# solenoid_drv.net
KiCad netlist of a schematic drawn in Altium Designer
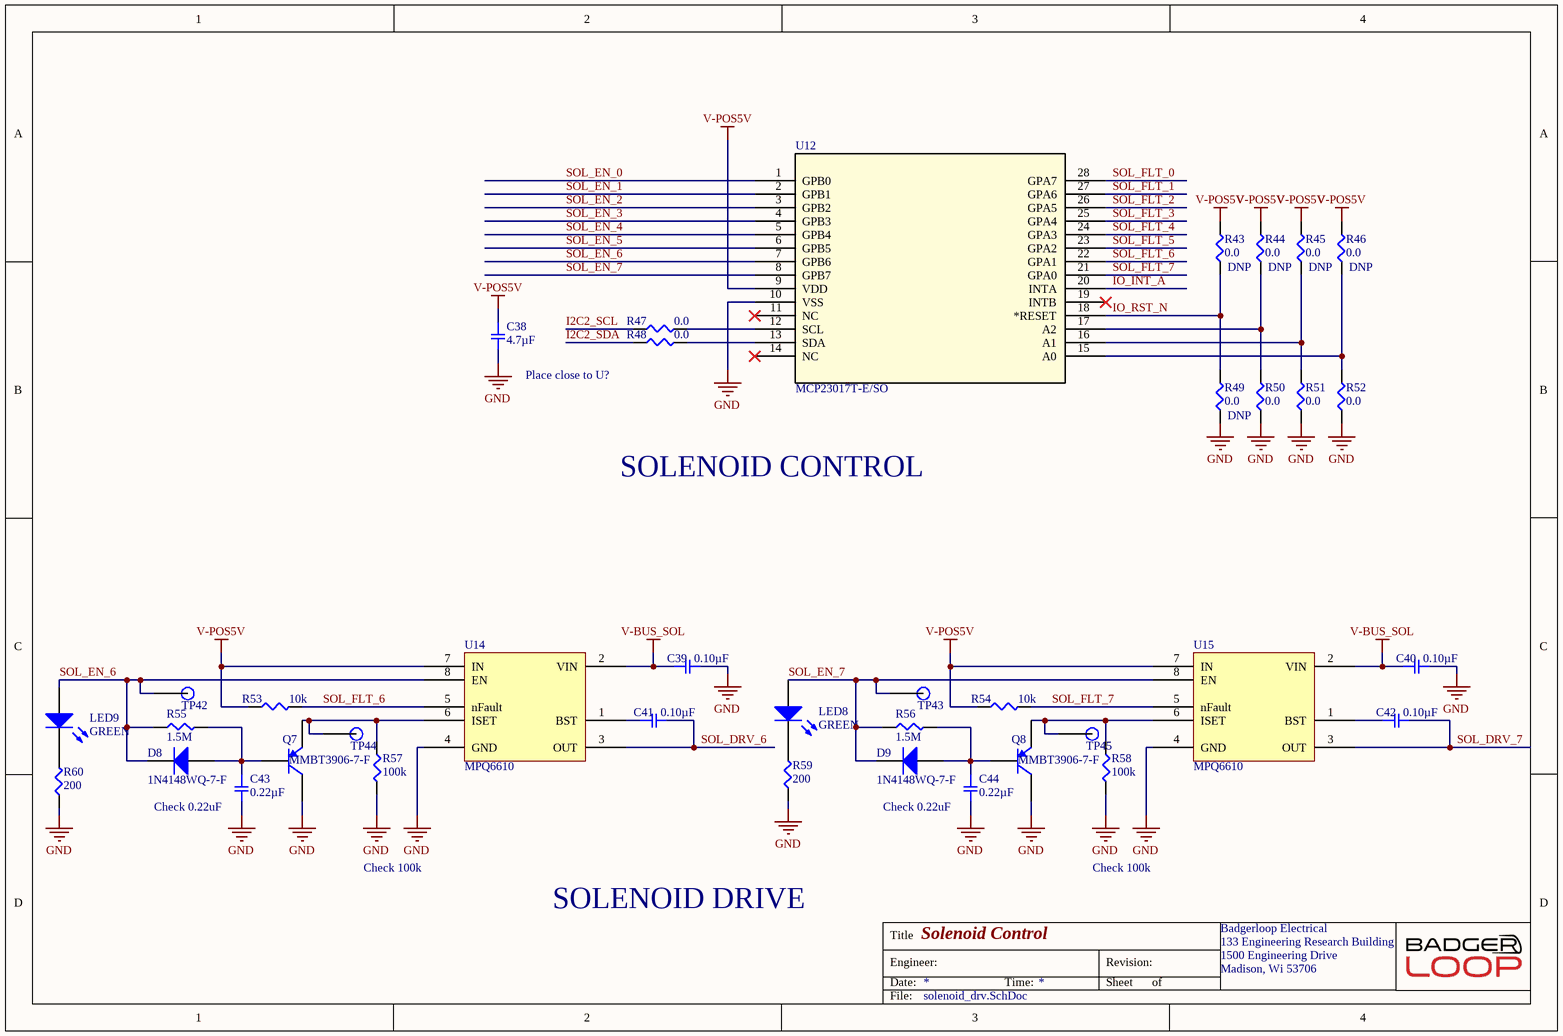
[diagram p0: solenoid_drv.SchDoc]

(export (version "E")
  (design (tool "Eeschema 10.0.6"))
  (components
    (comp (ref "C38")
      (value "4.7µF")
      (footprint "SMD-0805C")
      (description "CAP CER 4.7UF 6.3V X5R 0805")
      (fields
        (field (name "DIGI-KEY PART NUMBER") "490-9749-1-ND")
        (field (name "PART NUMBER") "GRM21BR60J475KA11L")
      )
      (libsource (lib "capacitor") (part "GRM21BR60J475KA11L"))
    )
    (comp (ref "C39")
      (value "0.10µF")
      (footprint "SMD-0805C")
      (description "CAP CER 0.1UF 10V U2J 0805")
      (fields
        (field (name "DIGI-KEY PART NUMBER") "490-11592-1-ND")
        (field (name "PART NUMBER") "GRM21B7U1A104JA01L")
      )
      (libsource (lib "capacitors") (part "GRM21B7U1A104JA01L"))
    )
    (comp (ref "C40")
      (value "0.10µF")
      (footprint "SMD-0805C")
      (description "CAP CER 0.1UF 10V U2J 0805")
      (fields
        (field (name "DIGI-KEY PART NUMBER") "490-11592-1-ND")
        (field (name "PART NUMBER") "GRM21B7U1A104JA01L")
      )
      (libsource (lib "capacitors") (part "GRM21B7U1A104JA01L"))
    )
    (comp (ref "C41")
      (value "0.10µF")
      (footprint "SMD-0805C")
      (description "CAP CER 0.1UF 10V U2J 0805")
      (fields
        (field (name "DIGI-KEY PART NUMBER") "490-11592-1-ND")
        (field (name "PART NUMBER") "GRM21B7U1A104JA01L")
      )
      (libsource (lib "capacitors") (part "GRM21B7U1A104JA01L"))
    )
    (comp (ref "C42")
      (value "0.10µF")
      (footprint "SMD-0805C")
      (description "CAP CER 0.1UF 10V U2J 0805")
      (fields
        (field (name "DIGI-KEY PART NUMBER") "490-11592-1-ND")
        (field (name "PART NUMBER") "GRM21B7U1A104JA01L")
      )
      (libsource (lib "capacitors") (part "GRM21B7U1A104JA01L"))
    )
    (comp (ref "C43")
      (value "0.22µF")
      (footprint "SMD-0805C")
      (description "CAP CER 0.22UF 10V X7R 0805")
      (fields
        (field (name "DIGI-KEY PART NUMBER") "490-4432-1-ND")
        (field (name "PART NUMBER") "LLA215R71A224MA14L")
      )
      (libsource (lib "capacitors") (part "LLA215R71A224MA14L"))
    )
    (comp (ref "C44")
      (value "0.22µF")
      (footprint "SMD-0805C")
      (description "CAP CER 0.22UF 10V X7R 0805")
      (fields
        (field (name "DIGI-KEY PART NUMBER") "490-4432-1-ND")
        (field (name "PART NUMBER") "LLA215R71A224MA14L")
      )
      (libsource (lib "capacitors") (part "LLA215R71A224MA14L"))
    )
    (comp (ref "D8")
      (value "1N4148WQ-7-F")
      (footprint "INDM3838X18N")
      (description "Diodes - General Purpose, Power, Switching SMT Fast Switching Diode")
      (fields (field (name "MANUFACTURER") "Diodes Inc."))
      (libsource (lib "misc") (part "1N4148WQ-7-F"))
    )
    (comp (ref "D9")
      (value "1N4148WQ-7-F")
      (footprint "INDM3838X18N")
      (description "Diodes - General Purpose, Power, Switching SMT Fast Switching Diode")
      (fields (field (name "MANUFACTURER") "Diodes Inc."))
      (libsource (lib "misc") (part "1N4148WQ-7-F"))
    )
    (comp (ref "LED8")
      (value "GREEN")
      (footprint "LED 0603 GREEN")
      (fields (field (name "MANUFACTURER") "Lite-On Inc."))
      (libsource (lib "misc") (part "LED GREEN 0603"))
    )
    (comp (ref "LED9")
      (value "GREEN")
      (footprint "LED 0603 GREEN")
      (fields (field (name "MANUFACTURER") "Lite-On Inc."))
      (libsource (lib "misc") (part "LED GREEN 0603"))
    )
    (comp (ref "Q7")
      (value "MMBT3906-7-F")
      (footprint "SOTFL103P240X110-3N")
      (fields (field (name "MANUFACTURER") "Diodes Zetex"))
      (libsource (lib "misc") (part "MMBT3906-7-F"))
    )
    (comp (ref "Q8")
      (value "MMBT3906-7-F")
      (footprint "SOTFL103P240X110-3N")
      (fields (field (name "MANUFACTURER") "Diodes Zetex"))
      (libsource (lib "misc") (part "MMBT3906-7-F"))
    )
    (comp (ref "R43")
      (value "0.0")
      (footprint "SMD-0805-RES")
      (description "RES SMD 0.0 OHM JUMPER 1/8W 0805")
      (fields
        (field (name "PART NUMBER") "ERJ-6GEY0R00V")
        (field (name "DIGI-KEY PART NUMBER") "P0.0ACT-ND")
        (field (name "DNP") "DNP")
      )
      (libsource (lib "resistors") (part "ERJ-6GEY0R00V"))
    )
    (comp (ref "R44")
      (value "0.0")
      (footprint "SMD-0805-RES")
      (description "RES SMD 0.0 OHM JUMPER 1/8W 0805")
      (fields
        (field (name "PART NUMBER") "ERJ-6GEY0R00V")
        (field (name "DIGI-KEY PART NUMBER") "P0.0ACT-ND")
        (field (name "DNP") "DNP")
      )
      (libsource (lib "resistors") (part "ERJ-6GEY0R00V"))
    )
    (comp (ref "R45")
      (value "0.0")
      (footprint "SMD-0805-RES")
      (description "RES SMD 0.0 OHM JUMPER 1/8W 0805")
      (fields
        (field (name "PART NUMBER") "ERJ-6GEY0R00V")
        (field (name "DIGI-KEY PART NUMBER") "P0.0ACT-ND")
        (field (name "DNP") "DNP")
      )
      (libsource (lib "resistors") (part "ERJ-6GEY0R00V"))
    )
    (comp (ref "R46")
      (value "0.0")
      (footprint "SMD-0805-RES")
      (description "RES SMD 0.0 OHM JUMPER 1/8W 0805")
      (fields
        (field (name "PART NUMBER") "ERJ-6GEY0R00V")
        (field (name "DIGI-KEY PART NUMBER") "P0.0ACT-ND")
        (field (name "DNP") "DNP")
      )
      (libsource (lib "resistors") (part "ERJ-6GEY0R00V"))
    )
    (comp (ref "R47")
      (value "0.0")
      (footprint "SMD-0805-RES")
      (description "RES SMD 0.0 OHM JUMPER 1/8W 0805")
      (fields (field (name "PART NUMBER") "ERJ-6GEY0R00V") (field (name "DIGI-KEY PART NUMBER") "P0.0ACT-ND"))
      (libsource (lib "resistors") (part "ERJ-6GEY0R00V"))
    )
    (comp (ref "R48")
      (value "0.0")
      (footprint "SMD-0805-RES")
      (description "RES SMD 0.0 OHM JUMPER 1/8W 0805")
      (fields (field (name "PART NUMBER") "ERJ-6GEY0R00V") (field (name "DIGI-KEY PART NUMBER") "P0.0ACT-ND"))
      (libsource (lib "resistors") (part "ERJ-6GEY0R00V"))
    )
    (comp (ref "R49")
      (value "0.0")
      (footprint "SMD-0805-RES")
      (description "RES SMD 0.0 OHM JUMPER 1/8W 0805")
      (fields
        (field (name "PART NUMBER") "ERJ-6GEY0R00V")
        (field (name "DIGI-KEY PART NUMBER") "P0.0ACT-ND")
        (field (name "DNP") "DNP")
      )
      (libsource (lib "resistors") (part "ERJ-6GEY0R00V"))
    )
    (comp (ref "R50")
      (value "0.0")
      (footprint "SMD-0805-RES")
      (description "RES SMD 0.0 OHM JUMPER 1/8W 0805")
      (fields (field (name "PART NUMBER") "ERJ-6GEY0R00V") (field (name "DIGI-KEY PART NUMBER") "P0.0ACT-ND"))
      (libsource (lib "resistors") (part "ERJ-6GEY0R00V"))
    )
    (comp (ref "R51")
      (value "0.0")
      (footprint "SMD-0805-RES")
      (description "RES SMD 0.0 OHM JUMPER 1/8W 0805")
      (fields (field (name "PART NUMBER") "ERJ-6GEY0R00V") (field (name "DIGI-KEY PART NUMBER") "P0.0ACT-ND"))
      (libsource (lib "resistors") (part "ERJ-6GEY0R00V"))
    )
    (comp (ref "R52")
      (value "0.0")
      (footprint "SMD-0805-RES")
      (description "RES SMD 0.0 OHM JUMPER 1/8W 0805")
      (fields (field (name "PART NUMBER") "ERJ-6GEY0R00V") (field (name "DIGI-KEY PART NUMBER") "P0.0ACT-ND"))
      (libsource (lib "resistors") (part "ERJ-6GEY0R00V"))
    )
    (comp (ref "R53")
      (value "10k")
      (footprint "SMD-0805-RES")
      (description "RES SMD 10K OHM 5% 1/2W 0805")
      (fields (field (name "PART NUMBER") "ERJ-P06J103V") (field (name "DIGI-KEY PART NUMBER") "P10KADCT-ND"))
      (libsource (lib "resistors") (part "ERJ-P06J103V"))
    )
    (comp (ref "R54")
      (value "10k")
      (footprint "SMD-0805-RES")
      (description "RES SMD 10K OHM 5% 1/2W 0805")
      (fields (field (name "PART NUMBER") "ERJ-P06J103V") (field (name "DIGI-KEY PART NUMBER") "P10KADCT-ND"))
      (libsource (lib "resistors") (part "ERJ-P06J103V"))
    )
    (comp (ref "R55")
      (value "1.5M")
      (footprint "SMD-0805-RES")
      (description "RES SMD 1.5M OHM 5% 1/8W 0805")
      (fields
        (field (name "PART NUMBER") "ERJ-6GEYJ155V")
        (field (name "DIGI-KEY PART NUMBER") "P1.5MACT-ND")
      )
      (libsource (lib "resistors") (part "ERJ-6GEYJ155V"))
    )
    (comp (ref "R56")
      (value "1.5M")
      (footprint "SMD-0805-RES")
      (description "RES SMD 1.5M OHM 5% 1/8W 0805")
      (fields
        (field (name "PART NUMBER") "ERJ-6GEYJ155V")
        (field (name "DIGI-KEY PART NUMBER") "P1.5MACT-ND")
      )
      (libsource (lib "resistors") (part "ERJ-6GEYJ155V"))
    )
    (comp (ref "R57")
      (value "100k")
      (footprint "SMD-0805-RES")
      (description "RES SMD 100K OHM 5% 1/2W 0805")
      (fields
        (field (name "PART NUMBER") "ERJ-P06J104V")
        (field (name "DIGI-KEY PART NUMBER") "P100KADCT-ND")
      )
      (libsource (lib "resistors") (part "ERJ-P06J104V"))
    )
    (comp (ref "R58")
      (value "100k")
      (footprint "SMD-0805-RES")
      (description "RES SMD 100K OHM 5% 1/2W 0805")
      (fields
        (field (name "PART NUMBER") "ERJ-P06J104V")
        (field (name "DIGI-KEY PART NUMBER") "P100KADCT-ND")
      )
      (libsource (lib "resistors") (part "ERJ-P06J104V"))
    )
    (comp (ref "R59")
      (value "200")
      (footprint "SMD-0805-RES")
      (description "RES SMD 200 OHM 1% 1/2W 0805")
      (fields
        (field (name "PART NUMBER") "ERJ-P06F2000V")
        (field (name "DIGI-KEY PART NUMBER") "P16064CT-ND")
      )
      (libsource (lib "resistors") (part "ERJ-P06F2000V"))
    )
    (comp (ref "R60")
      (value "200")
      (footprint "SMD-0805-RES")
      (description "RES SMD 200 OHM 1% 1/2W 0805")
      (fields
        (field (name "PART NUMBER") "ERJ-P06F2000V")
        (field (name "DIGI-KEY PART NUMBER") "P16064CT-ND")
      )
      (libsource (lib "resistors") (part "ERJ-P06F2000V"))
    )
    (comp (ref "TP42")
      (value "TP")
      (footprint "Test Point")
      (description "SMD TEST POINT")
      (libsource (lib "misc") (part "TP"))
    )
    (comp (ref "TP43")
      (value "TP")
      (footprint "Test Point")
      (description "SMD TEST POINT")
      (libsource (lib "misc") (part "TP"))
    )
    (comp (ref "TP44")
      (value "TP")
      (footprint "Test Point")
      (description "SMD TEST POINT")
      (libsource (lib "misc") (part "TP"))
    )
    (comp (ref "TP45")
      (value "TP")
      (footprint "Test Point")
      (description "SMD TEST POINT")
      (libsource (lib "misc") (part "TP"))
    )
    (comp (ref "U12")
      (value "MCP23017T-E/SO")
      (footprint "SOIC28-W_MC-M")
      (description "IC I/O EXPANDER I2C 16B 28SOIC")
      (fields (field (name "MANUFACTURER") "Microchip"))
      (libsource (lib "ic") (part "MCP23017T-E/SO"))
    )
    (comp (ref "U14")
      (value "MPQ6610")
      (footprint "SOP127P600X175-8N")
      (libsource (lib "ic") (part "MPQ6610"))
    )
    (comp (ref "U15")
      (value "MPQ6610")
      (footprint "SOP127P600X175-8N")
      (libsource (lib "ic") (part "MPQ6610"))
    )
  )
  (nets
    (net (code "1") (name "/I2C2_SCL") (class "Default")
      (node (ref "R47") (pin "1") (pinfunction "1_1") (pintype "passive"))
    )
    (net (code "2") (name "/I2C2_SDA") (class "Default")
      (node (ref "R48") (pin "1") (pinfunction "1_1") (pintype "passive"))
    )
    (net (code "3") (name "/IO_INT_A") (class "Default")
      (node (ref "U12") (pin "20") (pinfunction "INTA_20") (pintype "passive"))
    )
    (net (code "4") (name "/IO_RST_N") (class "Default")
      (node (ref "R43") (pin "1") (pinfunction "1_1") (pintype "passive"))
      (node (ref "R49") (pin "2") (pinfunction "2_2") (pintype "passive"))
      (node (ref "U12") (pin "18") (pinfunction "*RESET_18") (pintype "passive"))
    )
    (net (code "5") (name "/SOL_DRV_6") (class "Default")
      (node (ref "C41") (pin "2") (pinfunction "2_2") (pintype "passive"))
      (node (ref "U14") (pin "3") (pinfunction "OUT_3") (pintype "passive"))
    )
    (net (code "6") (name "/SOL_DRV_7") (class "Default")
      (node (ref "C42") (pin "2") (pinfunction "2_2") (pintype "passive"))
      (node (ref "U15") (pin "3") (pinfunction "OUT_3") (pintype "passive"))
    )
    (net (code "7") (name "/SOL_EN_0") (class "Default")
      (node (ref "U12") (pin "1") (pinfunction "GPB0_1") (pintype "passive"))
    )
    (net (code "8") (name "/SOL_EN_1") (class "Default")
      (node (ref "U12") (pin "2") (pinfunction "GPB1_2") (pintype "passive"))
    )
    (net (code "9") (name "/SOL_EN_2") (class "Default")
      (node (ref "U12") (pin "3") (pinfunction "GPB2_3") (pintype "passive"))
    )
    (net (code "10") (name "/SOL_EN_3") (class "Default")
      (node (ref "U12") (pin "4") (pinfunction "GPB3_4") (pintype "passive"))
    )
    (net (code "11") (name "/SOL_EN_4") (class "Default")
      (node (ref "U12") (pin "5") (pinfunction "GPB4_5") (pintype "passive"))
    )
    (net (code "12") (name "/SOL_EN_5") (class "Default")
      (node (ref "U12") (pin "6") (pinfunction "GPB5_6") (pintype "passive"))
    )
    (net (code "13") (name "/SOL_EN_6") (class "Default")
      (node (ref "D8") (pin "2") (pinfunction "K_2") (pintype "passive"))
      (node (ref "LED9") (pin "1") (pinfunction "A_1") (pintype "passive"))
      (node (ref "R55") (pin "1") (pinfunction "1_1") (pintype "passive"))
      (node (ref "TP42") (pin "1") (pinfunction "1_1") (pintype "passive"))
      (node (ref "U12") (pin "7") (pinfunction "GPB6_7") (pintype "passive"))
      (node (ref "U14") (pin "8") (pinfunction "EN_8") (pintype "power_in"))
    )
    (net (code "14") (name "/SOL_EN_7") (class "Default")
      (node (ref "D9") (pin "2") (pinfunction "K_2") (pintype "passive"))
      (node (ref "LED8") (pin "1") (pinfunction "A_1") (pintype "passive"))
      (node (ref "R56") (pin "1") (pinfunction "1_1") (pintype "passive"))
      (node (ref "TP43") (pin "1") (pinfunction "1_1") (pintype "passive"))
      (node (ref "U12") (pin "8") (pinfunction "GPB7_8") (pintype "passive"))
      (node (ref "U15") (pin "8") (pinfunction "EN_8") (pintype "power_in"))
    )
    (net (code "15") (name "/SOL_FLT_0") (class "Default")
      (node (ref "U12") (pin "28") (pinfunction "GPA7_28") (pintype "passive"))
    )
    (net (code "16") (name "/SOL_FLT_1") (class "Default")
      (node (ref "U12") (pin "27") (pinfunction "GPA6_27") (pintype "passive"))
    )
    (net (code "17") (name "/SOL_FLT_2") (class "Default")
      (node (ref "U12") (pin "26") (pinfunction "GPA5_26") (pintype "passive"))
    )
    (net (code "18") (name "/SOL_FLT_3") (class "Default")
      (node (ref "U12") (pin "25") (pinfunction "GPA4_25") (pintype "passive"))
    )
    (net (code "19") (name "/SOL_FLT_4") (class "Default")
      (node (ref "U12") (pin "24") (pinfunction "GPA3_24") (pintype "passive"))
    )
    (net (code "20") (name "/SOL_FLT_5") (class "Default")
      (node (ref "U12") (pin "23") (pinfunction "GPA2_23") (pintype "passive"))
    )
    (net (code "21") (name "/SOL_FLT_6") (class "Default")
      (node (ref "R53") (pin "2") (pinfunction "2_2") (pintype "passive"))
      (node (ref "U12") (pin "22") (pinfunction "GPA1_22") (pintype "passive"))
      (node (ref "U14") (pin "5") (pinfunction "nFault_5") (pintype "passive"))
    )
    (net (code "22") (name "/SOL_FLT_7") (class "Default")
      (node (ref "R54") (pin "2") (pinfunction "2_2") (pintype "passive"))
      (node (ref "U12") (pin "21") (pinfunction "GPA0_21") (pintype "passive"))
      (node (ref "U15") (pin "5") (pinfunction "nFault_5") (pintype "passive"))
    )
    (net (code "23") (name "GND") (class "Default")
      (node (ref "C38") (pin "2") (pinfunction "2_2") (pintype "passive"))
      (node (ref "C39") (pin "2") (pinfunction "2_2") (pintype "passive"))
      (node (ref "C40") (pin "2") (pinfunction "2_2") (pintype "passive"))
      (node (ref "C43") (pin "2") (pinfunction "2_2") (pintype "passive"))
      (node (ref "C44") (pin "2") (pinfunction "2_2") (pintype "passive"))
      (node (ref "Q7") (pin "3") (pinfunction "C_3") (pintype "passive"))
      (node (ref "Q8") (pin "3") (pinfunction "C_3") (pintype "passive"))
      (node (ref "R49") (pin "1") (pinfunction "1_1") (pintype "passive"))
      (node (ref "R50") (pin "1") (pinfunction "1_1") (pintype "passive"))
      (node (ref "R51") (pin "1") (pinfunction "1_1") (pintype "passive"))
      (node (ref "R52") (pin "1") (pinfunction "1_1") (pintype "passive"))
      (node (ref "R57") (pin "2") (pinfunction "2_2") (pintype "passive"))
      (node (ref "R58") (pin "2") (pinfunction "2_2") (pintype "passive"))
      (node (ref "R59") (pin "1") (pinfunction "1_1") (pintype "passive"))
      (node (ref "R60") (pin "1") (pinfunction "1_1") (pintype "passive"))
      (node (ref "U12") (pin "10") (pinfunction "VSS_10") (pintype "passive"))
      (node (ref "U14") (pin "4") (pinfunction "GND_4") (pintype "passive"))
      (node (ref "U15") (pin "4") (pinfunction "GND_4") (pintype "passive"))
    )
    (net (code "24") (name "Net-(D8-A)") (class "Default")
      (node (ref "C43") (pin "1") (pinfunction "1_1") (pintype "passive"))
      (node (ref "D8") (pin "1") (pinfunction "A_1") (pintype "passive"))
      (node (ref "Q7") (pin "1") (pinfunction "B_1") (pintype "passive"))
      (node (ref "R55") (pin "2") (pinfunction "2_2") (pintype "passive"))
    )
    (net (code "25") (name "Net-(D9-A)") (class "Default")
      (node (ref "C44") (pin "1") (pinfunction "1_1") (pintype "passive"))
      (node (ref "D9") (pin "1") (pinfunction "A_1") (pintype "passive"))
      (node (ref "Q8") (pin "1") (pinfunction "B_1") (pintype "passive"))
      (node (ref "R56") (pin "2") (pinfunction "2_2") (pintype "passive"))
    )
    (net (code "26") (name "Net-(LED8-K)") (class "Default")
      (node (ref "LED8") (pin "2") (pinfunction "K_2") (pintype "passive"))
      (node (ref "R59") (pin "2") (pinfunction "2_2") (pintype "passive"))
    )
    (net (code "27") (name "Net-(LED9-K)") (class "Default")
      (node (ref "LED9") (pin "2") (pinfunction "K_2") (pintype "passive"))
      (node (ref "R60") (pin "2") (pinfunction "2_2") (pintype "passive"))
    )
    (net (code "28") (name "Net-(Q7-E)") (class "Default")
      (node (ref "Q7") (pin "2") (pinfunction "E_2") (pintype "passive"))
      (node (ref "R57") (pin "1") (pinfunction "1_1") (pintype "passive"))
      (node (ref "TP44") (pin "1") (pinfunction "1_1") (pintype "passive"))
      (node (ref "U14") (pin "6") (pinfunction "ISET_6") (pintype "power_in"))
    )
    (net (code "29") (name "Net-(Q8-E)") (class "Default")
      (node (ref "Q8") (pin "2") (pinfunction "E_2") (pintype "passive"))
      (node (ref "R58") (pin "1") (pinfunction "1_1") (pintype "passive"))
      (node (ref "TP45") (pin "1") (pinfunction "1_1") (pintype "passive"))
      (node (ref "U15") (pin "6") (pinfunction "ISET_6") (pintype "power_in"))
    )
    (net (code "30") (name "Net-(U12-A0)") (class "Default")
      (node (ref "R46") (pin "1") (pinfunction "1_1") (pintype "passive"))
      (node (ref "R52") (pin "2") (pinfunction "2_2") (pintype "passive"))
      (node (ref "U12") (pin "15") (pinfunction "A0_15") (pintype "passive"))
    )
    (net (code "31") (name "Net-(U12-A1)") (class "Default")
      (node (ref "R45") (pin "1") (pinfunction "1_1") (pintype "passive"))
      (node (ref "R51") (pin "2") (pinfunction "2_2") (pintype "passive"))
      (node (ref "U12") (pin "16") (pinfunction "A1_16") (pintype "passive"))
    )
    (net (code "32") (name "Net-(U12-A2)") (class "Default")
      (node (ref "R44") (pin "1") (pinfunction "1_1") (pintype "passive"))
      (node (ref "R50") (pin "2") (pinfunction "2_2") (pintype "passive"))
      (node (ref "U12") (pin "17") (pinfunction "A2_17") (pintype "passive"))
    )
    (net (code "33") (name "Net-(U12-SCL)") (class "Default")
      (node (ref "R47") (pin "2") (pinfunction "2_2") (pintype "passive"))
      (node (ref "U12") (pin "12") (pinfunction "SCL_12") (pintype "passive"))
    )
    (net (code "34") (name "Net-(U12-SDA)") (class "Default")
      (node (ref "R48") (pin "2") (pinfunction "2_2") (pintype "passive"))
      (node (ref "U12") (pin "13") (pinfunction "SDA_13") (pintype "passive"))
    )
    (net (code "35") (name "Net-(U14-BST)") (class "Default")
      (node (ref "C41") (pin "1") (pinfunction "1_1") (pintype "passive"))
      (node (ref "U14") (pin "1") (pinfunction "BST_1") (pintype "passive"))
    )
    (net (code "36") (name "Net-(U15-BST)") (class "Default")
      (node (ref "C42") (pin "1") (pinfunction "1_1") (pintype "passive"))
      (node (ref "U15") (pin "1") (pinfunction "BST_1") (pintype "passive"))
    )
    (net (code "37") (name "V-BUS_SOL") (class "Default")
      (node (ref "C39") (pin "1") (pinfunction "1_1") (pintype "passive"))
      (node (ref "C40") (pin "1") (pinfunction "1_1") (pintype "passive"))
      (node (ref "U14") (pin "2") (pinfunction "VIN_2") (pintype "passive"))
      (node (ref "U15") (pin "2") (pinfunction "VIN_2") (pintype "passive"))
    )
    (net (code "38") (name "V-POS5V") (class "Default")
      (node (ref "C38") (pin "1") (pinfunction "1_1") (pintype "passive"))
      (node (ref "R43") (pin "2") (pinfunction "2_2") (pintype "passive"))
      (node (ref "R44") (pin "2") (pinfunction "2_2") (pintype "passive"))
      (node (ref "R45") (pin "2") (pinfunction "2_2") (pintype "passive"))
      (node (ref "R46") (pin "2") (pinfunction "2_2") (pintype "passive"))
      (node (ref "R53") (pin "1") (pinfunction "1_1") (pintype "passive"))
      (node (ref "R54") (pin "1") (pinfunction "1_1") (pintype "passive"))
      (node (ref "U12") (pin "9") (pinfunction "VDD_9") (pintype "passive"))
      (node (ref "U14") (pin "7") (pinfunction "IN_7") (pintype "passive"))
      (node (ref "U15") (pin "7") (pinfunction "IN_7") (pintype "passive"))
    )
    (net (code "39") (name "unconnected-(U12-INTB-Pad19)") (class "Default")
      (node (ref "U12") (pin "19") (pinfunction "INTB_19") (pintype "passive+no_connect"))
    )
    (net (code "40") (name "unconnected-(U12-NC-Pad11)") (class "Default")
      (node (ref "U12") (pin "11") (pinfunction "NC_11") (pintype "passive+no_connect"))
    )
    (net (code "41") (name "unconnected-(U12-NC-Pad14)") (class "Default")
      (node (ref "U12") (pin "14") (pinfunction "NC_14") (pintype "passive+no_connect"))
    )
  )
)
